# RPi-ShieldBridge_v10.net
KiCad netlist of a schematic drawn in EAGLE
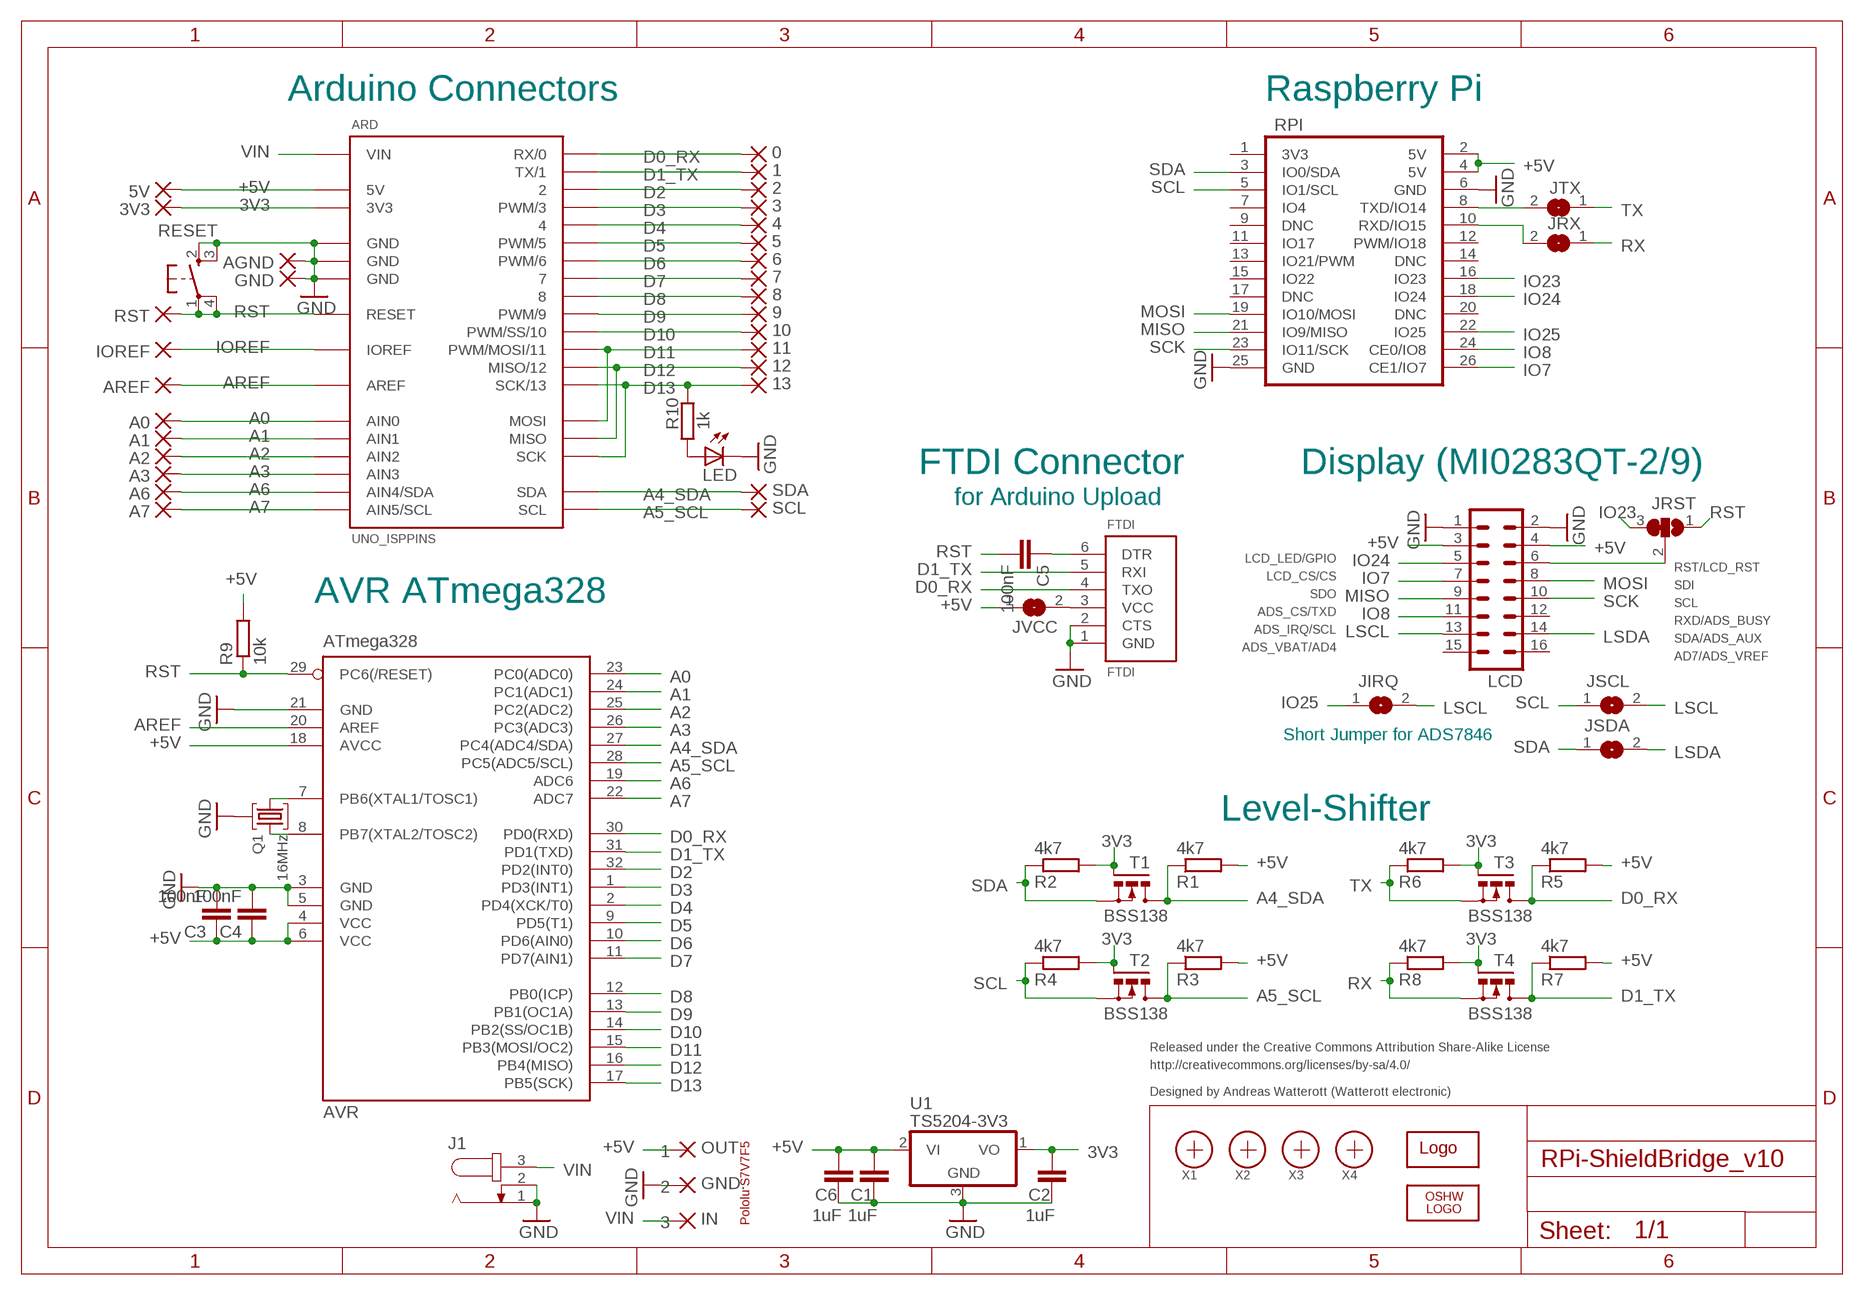
[diagram p0: schematic, sheet 1]

(export (version "E")
  (design (tool "Eeschema 10.0.6"))
  (components
    (comp (ref "0")
      (value "WIREPAD1,6/0,9")
      (footprint "eagle-import:1,6_0,9")
      (libsource (lib "eagle-import") (part "WIREPAD1,6/0,9"))
    )
    (comp (ref "1")
      (value "WIREPAD1,6/0,9")
      (footprint "eagle-import:1,6_0,9")
      (libsource (lib "eagle-import") (part "WIREPAD1,6/0,9"))
    )
    (comp (ref "2")
      (value "WIREPAD1,6/0,9")
      (footprint "eagle-import:1,6_0,9")
      (libsource (lib "eagle-import") (part "WIREPAD1,6/0,9"))
    )
    (comp (ref "3")
      (value "WIREPAD1,6/0,9")
      (footprint "eagle-import:1,6_0,9")
      (libsource (lib "eagle-import") (part "WIREPAD1,6/0,9"))
    )
    (comp (ref "3V3")
      (value "WIREPAD1,6/0,9")
      (footprint "eagle-import:1,6_0,9")
      (libsource (lib "eagle-import") (part "WIREPAD1,6/0,9"))
    )
    (comp (ref "4")
      (value "WIREPAD1,6/0,9")
      (footprint "eagle-import:1,6_0,9")
      (libsource (lib "eagle-import") (part "WIREPAD1,6/0,9"))
    )
    (comp (ref "5")
      (value "WIREPAD1,6/0,9")
      (footprint "eagle-import:1,6_0,9")
      (libsource (lib "eagle-import") (part "WIREPAD1,6/0,9"))
    )
    (comp (ref "5V")
      (value "WIREPAD1,6/0,9")
      (footprint "eagle-import:1,6_0,9")
      (libsource (lib "eagle-import") (part "WIREPAD1,6/0,9"))
    )
    (comp (ref "6")
      (value "WIREPAD1,6/0,9")
      (footprint "eagle-import:1,6_0,9")
      (libsource (lib "eagle-import") (part "WIREPAD1,6/0,9"))
    )
    (comp (ref "7")
      (value "WIREPAD1,6/0,9")
      (footprint "eagle-import:1,6_0,9")
      (libsource (lib "eagle-import") (part "WIREPAD1,6/0,9"))
    )
    (comp (ref "8")
      (value "WIREPAD1,6/0,9")
      (footprint "eagle-import:1,6_0,9")
      (libsource (lib "eagle-import") (part "WIREPAD1,6/0,9"))
    )
    (comp (ref "9")
      (value "WIREPAD1,6/0,9")
      (footprint "eagle-import:1,6_0,9")
      (libsource (lib "eagle-import") (part "WIREPAD1,6/0,9"))
    )
    (comp (ref "10")
      (value "WIREPAD1,6/0,9")
      (footprint "eagle-import:1,6_0,9")
      (libsource (lib "eagle-import") (part "WIREPAD1,6/0,9"))
    )
    (comp (ref "11")
      (value "WIREPAD1,6/0,9")
      (footprint "eagle-import:1,6_0,9")
      (libsource (lib "eagle-import") (part "WIREPAD1,6/0,9"))
    )
    (comp (ref "12")
      (value "WIREPAD1,6/0,9")
      (footprint "eagle-import:1,6_0,9")
      (libsource (lib "eagle-import") (part "WIREPAD1,6/0,9"))
    )
    (comp (ref "13")
      (value "WIREPAD1,6/0,9")
      (footprint "eagle-import:1,6_0,9")
      (libsource (lib "eagle-import") (part "WIREPAD1,6/0,9"))
    )
    (comp (ref "A0")
      (value "WIREPAD1,6/0,9")
      (footprint "eagle-import:1,6_0,9")
      (libsource (lib "eagle-import") (part "WIREPAD1,6/0,9"))
    )
    (comp (ref "A1")
      (value "WIREPAD1,6/0,9")
      (footprint "eagle-import:1,6_0,9")
      (libsource (lib "eagle-import") (part "WIREPAD1,6/0,9"))
    )
    (comp (ref "A2")
      (value "WIREPAD1,6/0,9")
      (footprint "eagle-import:1,6_0,9")
      (libsource (lib "eagle-import") (part "WIREPAD1,6/0,9"))
    )
    (comp (ref "A3")
      (value "WIREPAD1,6/0,9")
      (footprint "eagle-import:1,6_0,9")
      (libsource (lib "eagle-import") (part "WIREPAD1,6/0,9"))
    )
    (comp (ref "A6")
      (value "WIREPAD1,6/0,9")
      (footprint "eagle-import:1,6_0,9")
      (libsource (lib "eagle-import") (part "WIREPAD1,6/0,9"))
    )
    (comp (ref "A7")
      (value "WIREPAD1,6/0,9")
      (footprint "eagle-import:1,6_0,9")
      (libsource (lib "eagle-import") (part "WIREPAD1,6/0,9"))
    )
    (comp (ref "AGND")
      (value "WIREPAD1,6/0,9")
      (footprint "eagle-import:1,6_0,9")
      (libsource (lib "eagle-import") (part "WIREPAD1,6/0,9"))
    )
    (comp (ref "ARD")
      (value "UNO_ISPPINS")
      (footprint "eagle-import:UNO_ISP3")
      (libsource (lib "eagle-import") (part "UNO_ISPPINS"))
    )
    (comp (ref "AREF")
      (value "WIREPAD1,6/0,9")
      (footprint "eagle-import:1,6_0,9")
      (libsource (lib "eagle-import") (part "WIREPAD1,6/0,9"))
    )
    (comp (ref "AVR")
      (value "ATmega328")
      (footprint "eagle-import:TQFP32-08")
      (fields (field (name "MPN") "ATMEGA8-16AU"))
      (libsource (lib "eagle-import") (part "MEGA8-AI"))
    )
    (comp (ref "C1")
      (value "1uF")
      (footprint "eagle-import:C0603")
      (libsource (lib "eagle-import") (part "C-EUC0603"))
    )
    (comp (ref "C2")
      (value "1uF")
      (footprint "eagle-import:C0603")
      (libsource (lib "eagle-import") (part "C-EUC0603"))
    )
    (comp (ref "C3")
      (value "100nF")
      (footprint "eagle-import:C0603")
      (libsource (lib "eagle-import") (part "C-EUC0603"))
    )
    (comp (ref "C4")
      (value "100nF")
      (footprint "eagle-import:C0603")
      (libsource (lib "eagle-import") (part "C-EUC0603"))
    )
    (comp (ref "C5")
      (value "100nF")
      (footprint "eagle-import:C0603")
      (libsource (lib "eagle-import") (part "C-EUC0603"))
    )
    (comp (ref "C6")
      (value "1uF")
      (footprint "eagle-import:C0603")
      (libsource (lib "eagle-import") (part "C-EUC0603"))
    )
    (comp (ref "FTDI")
      (value "FTDI")
      (footprint "eagle-import:FTDI")
      (libsource (lib "eagle-import") (part "FTDI"))
    )
    (comp (ref "GND")
      (value "WIREPAD1,6/0,9")
      (footprint "eagle-import:1,6_0,9")
      (libsource (lib "eagle-import") (part "WIREPAD1,6/0,9"))
    )
    (comp (ref "GND.")
      (value "2")
      (footprint "eagle-import:1,6_0,9")
      (libsource (lib "eagle-import") (part "WIREPAD1,6/0,9"))
    )
    (comp (ref "IN")
      (value "3")
      (footprint "eagle-import:1,6_0,9")
      (libsource (lib "eagle-import") (part "WIREPAD1,6/0,9"))
    )
    (comp (ref "IOREF")
      (value "WIREPAD1,6/0,9")
      (footprint "eagle-import:1,6_0,9")
      (libsource (lib "eagle-import") (part "WIREPAD1,6/0,9"))
    )
    (comp (ref "J1")
      (value "DC-JACK\"\"")
      (footprint "eagle-import:DC-JACK")
      (libsource (lib "eagle-import") (part "DC-JACK{dblquote}{dblquote}"))
    )
    (comp (ref "JIRQ")
      (value "SJ")
      (footprint "eagle-import:SJ")
      (libsource (lib "eagle-import") (part "SJ"))
    )
    (comp (ref "JRST")
      (value "SJ2W")
      (footprint "eagle-import:SJ_2")
      (libsource (lib "eagle-import") (part "SJ2W"))
    )
    (comp (ref "JRX") (value "SJ") (footprint "eagle-import:SJ") (libsource (lib "eagle-import") (part "SJ")))
    (comp (ref "JSCL")
      (value "SJ")
      (footprint "eagle-import:SJ")
      (libsource (lib "eagle-import") (part "SJ"))
    )
    (comp (ref "JSDA")
      (value "SJ")
      (footprint "eagle-import:SJ")
      (libsource (lib "eagle-import") (part "SJ"))
    )
    (comp (ref "JTX") (value "SJ") (footprint "eagle-import:SJ") (libsource (lib "eagle-import") (part "SJ")))
    (comp (ref "JVCC")
      (value "SJ")
      (footprint "eagle-import:SJ")
      (libsource (lib "eagle-import") (part "SJ"))
    )
    (comp (ref "LCD")
      (value "MA08-2")
      (footprint "eagle-import:MA08-2")
      (libsource (lib "eagle-import") (part "MA08-2"))
    )
    (comp (ref "LED")
      (value "LEDCHIPLED_0603")
      (footprint "eagle-import:CHIPLED_0603")
      (libsource (lib "eagle-import") (part "LEDCHIPLED_0603"))
    )
    (comp (ref "LOGO1")
      (value "OSHW_LOGO_6MILX0150-NT")
      (footprint "eagle-import:OSHW_6X150_NOTEXT")
      (libsource (lib "eagle-import") (part "OSHW_LOGO_6MILX0150-NT"))
    )
    (comp (ref "OUT")
      (value "1")
      (footprint "eagle-import:1,6_0,9")
      (libsource (lib "eagle-import") (part "WIREPAD1,6/0,9"))
    )
    (comp (ref "Q1")
      (value "16MHz")
      (footprint "eagle-import:SMD_OSC_35X15")
      (libsource (lib "eagle-import") (part "SMD_OSC2"))
    )
    (comp (ref "R1")
      (value "4k7")
      (footprint "eagle-import:R0603")
      (libsource (lib "eagle-import") (part "R-EU_R0603"))
    )
    (comp (ref "R2")
      (value "4k7")
      (footprint "eagle-import:R0603")
      (libsource (lib "eagle-import") (part "R-EU_R0603"))
    )
    (comp (ref "R3")
      (value "4k7")
      (footprint "eagle-import:R0603")
      (libsource (lib "eagle-import") (part "R-EU_R0603"))
    )
    (comp (ref "R4")
      (value "4k7")
      (footprint "eagle-import:R0603")
      (libsource (lib "eagle-import") (part "R-EU_R0603"))
    )
    (comp (ref "R5")
      (value "4k7")
      (footprint "eagle-import:R0603")
      (libsource (lib "eagle-import") (part "R-EU_R0603"))
    )
    (comp (ref "R6")
      (value "4k7")
      (footprint "eagle-import:R0603")
      (libsource (lib "eagle-import") (part "R-EU_R0603"))
    )
    (comp (ref "R7")
      (value "4k7")
      (footprint "eagle-import:R0603")
      (libsource (lib "eagle-import") (part "R-EU_R0603"))
    )
    (comp (ref "R8")
      (value "4k7")
      (footprint "eagle-import:R0603")
      (libsource (lib "eagle-import") (part "R-EU_R0603"))
    )
    (comp (ref "R9")
      (value "10k")
      (footprint "eagle-import:R0603")
      (libsource (lib "eagle-import") (part "R-EU_R0603"))
    )
    (comp (ref "R10")
      (value "1k")
      (footprint "eagle-import:R0603")
      (libsource (lib "eagle-import") (part "R-EU_R0603"))
    )
    (comp (ref "RESET")
      (value "SW_SMDS")
      (footprint "eagle-import:SW_SMD4@1")
      (libsource (lib "eagle-import") (part "SW_SMDS"))
    )
    (comp (ref "RPI")
      (value "RPI")
      (footprint "eagle-import:RPI")
      (libsource (lib "eagle-import") (part "RPI"))
    )
    (comp (ref "RST")
      (value "WIREPAD1,6/0,9")
      (footprint "eagle-import:1,6_0,9")
      (libsource (lib "eagle-import") (part "WIREPAD1,6/0,9"))
    )
    (comp (ref "SCL")
      (value "WIREPAD1,6/0,9")
      (footprint "eagle-import:1,6_0,9")
      (libsource (lib "eagle-import") (part "WIREPAD1,6/0,9"))
    )
    (comp (ref "SDA")
      (value "WIREPAD1,6/0,9")
      (footprint "eagle-import:1,6_0,9")
      (libsource (lib "eagle-import") (part "WIREPAD1,6/0,9"))
    )
    (comp (ref "T1")
      (value "BSS138")
      (footprint "eagle-import:MICRO3")
      (libsource (lib "eagle-import") (part "IRLML2502"))
    )
    (comp (ref "T2")
      (value "BSS138")
      (footprint "eagle-import:MICRO3")
      (libsource (lib "eagle-import") (part "IRLML2502"))
    )
    (comp (ref "T3")
      (value "BSS138")
      (footprint "eagle-import:MICRO3")
      (libsource (lib "eagle-import") (part "IRLML2502"))
    )
    (comp (ref "T4")
      (value "BSS138")
      (footprint "eagle-import:MICRO3")
      (libsource (lib "eagle-import") (part "IRLML2502"))
    )
    (comp (ref "U$1")
      (value "WE-LOGO")
      (footprint "eagle-import:WE-LOGO")
      (libsource (lib "eagle-import") (part "WE-LOGOPLACE"))
    )
    (comp (ref "U1")
      (value "TS5204-3V3")
      (footprint "eagle-import:SOT23")
      (libsource (lib "eagle-import") (part "TS5204"))
    )
    (comp (ref "X1")
      (value "PASSER")
      (footprint "eagle-import:PASSER")
      (libsource (lib "eagle-import") (part "PASSER"))
    )
    (comp (ref "X2")
      (value "PASSER")
      (footprint "eagle-import:PASSER")
      (libsource (lib "eagle-import") (part "PASSER"))
    )
    (comp (ref "X3")
      (value "PASSER")
      (footprint "eagle-import:PASSER")
      (libsource (lib "eagle-import") (part "PASSER"))
    )
    (comp (ref "X4")
      (value "PASSER")
      (footprint "eagle-import:PASSER")
      (libsource (lib "eagle-import") (part "PASSER"))
    )
  )
  (nets
    (net (code "1") (name "/+5V") (class "Default")
      (node (ref "5V") (pin "1") (pinfunction "P_1") (pintype "passive"))
      (node (ref "ARD") (pin "5V") (pinfunction "5V_5V") (pintype "power_in"))
      (node (ref "AVR") (pin "18") (pinfunction "AVCC_18") (pintype "power_in"))
      (node (ref "AVR") (pin "4") (pinfunction "VCC_4") (pintype "power_in"))
      (node (ref "AVR") (pin "6") (pinfunction "VCC_6") (pintype "power_in"))
      (node (ref "C1") (pin "1") (pinfunction "1_1") (pintype "passive"))
      (node (ref "C3") (pin "1") (pinfunction "1_1") (pintype "passive"))
      (node (ref "C4") (pin "1") (pinfunction "1_1") (pintype "passive"))
      (node (ref "C6") (pin "1") (pinfunction "1_1") (pintype "passive"))
      (node (ref "JVCC") (pin "1") (pinfunction "1_1") (pintype "passive"))
      (node (ref "LCD") (pin "3") (pinfunction "3_3") (pintype "passive"))
      (node (ref "LCD") (pin "4") (pinfunction "4_4") (pintype "passive"))
      (node (ref "OUT") (pin "1") (pinfunction "P_1") (pintype "passive"))
      (node (ref "R1") (pin "2") (pinfunction "2_2") (pintype "passive"))
      (node (ref "R3") (pin "2") (pinfunction "2_2") (pintype "passive"))
      (node (ref "R5") (pin "2") (pinfunction "2_2") (pintype "passive"))
      (node (ref "R7") (pin "2") (pinfunction "2_2") (pintype "passive"))
      (node (ref "R9") (pin "2") (pinfunction "2_2") (pintype "passive"))
      (node (ref "RPI") (pin "2") (pinfunction "5V_2") (pintype "passive"))
      (node (ref "RPI") (pin "4") (pinfunction "5V_4") (pintype "passive"))
      (node (ref "U1") (pin "2") (pinfunction "VI_2") (pintype "input"))
    )
    (net (code "2") (name "/3V3") (class "Default")
      (node (ref "3V3") (pin "1") (pinfunction "P_1") (pintype "passive"))
      (node (ref "ARD") (pin "3V3") (pinfunction "3V3_3V3") (pintype "power_in"))
      (node (ref "C2") (pin "1") (pinfunction "1_1") (pintype "passive"))
      (node (ref "R2") (pin "2") (pinfunction "2_2") (pintype "passive"))
      (node (ref "R4") (pin "2") (pinfunction "2_2") (pintype "passive"))
      (node (ref "R6") (pin "2") (pinfunction "2_2") (pintype "passive"))
      (node (ref "R8") (pin "2") (pinfunction "2_2") (pintype "passive"))
      (node (ref "T1") (pin "1") (pinfunction "G_1") (pintype "passive"))
      (node (ref "T2") (pin "1") (pinfunction "G_1") (pintype "passive"))
      (node (ref "T3") (pin "1") (pinfunction "G_1") (pintype "passive"))
      (node (ref "T4") (pin "1") (pinfunction "G_1") (pintype "passive"))
      (node (ref "U1") (pin "1") (pinfunction "VO_1") (pintype "passive"))
    )
    (net (code "3") (name "/A0") (class "Default")
      (node (ref "A0") (pin "1") (pinfunction "P_1") (pintype "passive"))
      (node (ref "ARD") (pin "AIN0") (pinfunction "AIN0_AIN0") (pintype "bidirectional"))
      (node (ref "AVR") (pin "23") (pinfunction "PC0(ADC0)_23") (pintype "bidirectional"))
    )
    (net (code "4") (name "/A1") (class "Default")
      (node (ref "A1") (pin "1") (pinfunction "P_1") (pintype "passive"))
      (node (ref "ARD") (pin "AIN1") (pinfunction "AIN1_AIN1") (pintype "bidirectional"))
      (node (ref "AVR") (pin "24") (pinfunction "PC1(ADC1)_24") (pintype "bidirectional"))
    )
    (net (code "5") (name "/A2") (class "Default")
      (node (ref "A2") (pin "1") (pinfunction "P_1") (pintype "passive"))
      (node (ref "ARD") (pin "AIN2") (pinfunction "AIN2_AIN2") (pintype "bidirectional"))
      (node (ref "AVR") (pin "25") (pinfunction "PC2(ADC2)_25") (pintype "bidirectional"))
    )
    (net (code "6") (name "/A3") (class "Default")
      (node (ref "A3") (pin "1") (pinfunction "P_1") (pintype "passive"))
      (node (ref "ARD") (pin "AIN3") (pinfunction "AIN3_AIN3") (pintype "bidirectional"))
      (node (ref "AVR") (pin "26") (pinfunction "PC3(ADC3)_26") (pintype "bidirectional"))
    )
    (net (code "7") (name "/A4_SDA") (class "Default")
      (node (ref "ARD") (pin "SDA") (pinfunction "SDA_SDA") (pintype "bidirectional"))
      (node (ref "AVR") (pin "27") (pinfunction "PC4(ADC4/SDA)_27") (pintype "bidirectional"))
      (node (ref "R1") (pin "1") (pinfunction "1_1") (pintype "passive"))
      (node (ref "SDA") (pin "1") (pinfunction "P_1") (pintype "passive"))
      (node (ref "T1") (pin "3") (pinfunction "D_3") (pintype "passive"))
    )
    (net (code "8") (name "/A5_SCL") (class "Default")
      (node (ref "ARD") (pin "SCL") (pinfunction "SCL_SCL") (pintype "bidirectional"))
      (node (ref "AVR") (pin "28") (pinfunction "PC5(ADC5/SCL)_28") (pintype "bidirectional"))
      (node (ref "R3") (pin "1") (pinfunction "1_1") (pintype "passive"))
      (node (ref "SCL") (pin "1") (pinfunction "P_1") (pintype "passive"))
      (node (ref "T2") (pin "3") (pinfunction "D_3") (pintype "passive"))
    )
    (net (code "9") (name "/A6") (class "Default")
      (node (ref "A6") (pin "1") (pinfunction "P_1") (pintype "passive"))
      (node (ref "ARD") (pin "AIN4") (pinfunction "AIN4/SDA_AIN4") (pintype "bidirectional"))
      (node (ref "AVR") (pin "19") (pinfunction "ADC6_19") (pintype "bidirectional"))
    )
    (net (code "10") (name "/A7") (class "Default")
      (node (ref "A7") (pin "1") (pinfunction "P_1") (pintype "passive"))
      (node (ref "ARD") (pin "AIN5") (pinfunction "AIN5/SCL_AIN5") (pintype "bidirectional"))
      (node (ref "AVR") (pin "22") (pinfunction "ADC7_22") (pintype "bidirectional"))
    )
    (net (code "11") (name "/AREF") (class "Default")
      (node (ref "ARD") (pin "AREF") (pinfunction "AREF_AREF") (pintype "power_in"))
      (node (ref "AREF") (pin "1") (pinfunction "P_1") (pintype "passive"))
      (node (ref "AVR") (pin "20") (pinfunction "AREF_20") (pintype "passive"))
    )
    (net (code "12") (name "/D0_RX") (class "Default")
      (node (ref "0") (pin "1") (pinfunction "P_1") (pintype "passive"))
      (node (ref "ARD") (pin "0") (pinfunction "RX/0_0") (pintype "bidirectional"))
      (node (ref "AVR") (pin "30") (pinfunction "PD0(RXD)_30") (pintype "bidirectional"))
      (node (ref "FTDI") (pin "4") (pinfunction "TXO_4") (pintype "bidirectional"))
      (node (ref "R5") (pin "1") (pinfunction "1_1") (pintype "passive"))
      (node (ref "T3") (pin "3") (pinfunction "D_3") (pintype "passive"))
    )
    (net (code "13") (name "/D1_TX") (class "Default")
      (node (ref "1") (pin "1") (pinfunction "P_1") (pintype "passive"))
      (node (ref "ARD") (pin "1") (pinfunction "TX/1_1") (pintype "bidirectional"))
      (node (ref "AVR") (pin "31") (pinfunction "PD1(TXD)_31") (pintype "bidirectional"))
      (node (ref "FTDI") (pin "5") (pinfunction "RXI_5") (pintype "bidirectional"))
      (node (ref "R7") (pin "1") (pinfunction "1_1") (pintype "passive"))
      (node (ref "T4") (pin "3") (pinfunction "D_3") (pintype "passive"))
    )
    (net (code "14") (name "/D2") (class "Default")
      (node (ref "2") (pin "1") (pinfunction "P_1") (pintype "passive"))
      (node (ref "ARD") (pin "2") (pinfunction "2_2") (pintype "bidirectional"))
      (node (ref "AVR") (pin "32") (pinfunction "PD2(INT0)_32") (pintype "bidirectional"))
    )
    (net (code "15") (name "/D3") (class "Default")
      (node (ref "3") (pin "1") (pinfunction "P_1") (pintype "passive"))
      (node (ref "ARD") (pin "3") (pinfunction "PWM/3_3") (pintype "bidirectional"))
      (node (ref "AVR") (pin "1") (pinfunction "PD3(INT1)_1") (pintype "bidirectional"))
    )
    (net (code "16") (name "/D4") (class "Default")
      (node (ref "4") (pin "1") (pinfunction "P_1") (pintype "passive"))
      (node (ref "ARD") (pin "4") (pinfunction "4_4") (pintype "bidirectional"))
      (node (ref "AVR") (pin "2") (pinfunction "PD4(XCK/T0)_2") (pintype "bidirectional"))
    )
    (net (code "17") (name "/D5") (class "Default")
      (node (ref "5") (pin "1") (pinfunction "P_1") (pintype "passive"))
      (node (ref "ARD") (pin "5") (pinfunction "PWM/5_5") (pintype "bidirectional"))
      (node (ref "AVR") (pin "9") (pinfunction "PD5(T1)_9") (pintype "bidirectional"))
    )
    (net (code "18") (name "/D6") (class "Default")
      (node (ref "6") (pin "1") (pinfunction "P_1") (pintype "passive"))
      (node (ref "ARD") (pin "6") (pinfunction "PWM/6_6") (pintype "bidirectional"))
      (node (ref "AVR") (pin "10") (pinfunction "PD6(AIN0)_10") (pintype "bidirectional"))
    )
    (net (code "19") (name "/D7") (class "Default")
      (node (ref "7") (pin "1") (pinfunction "P_1") (pintype "passive"))
      (node (ref "ARD") (pin "7") (pinfunction "7_7") (pintype "bidirectional"))
      (node (ref "AVR") (pin "11") (pinfunction "PD7(AIN1)_11") (pintype "bidirectional"))
    )
    (net (code "20") (name "/D8") (class "Default")
      (node (ref "8") (pin "1") (pinfunction "P_1") (pintype "passive"))
      (node (ref "ARD") (pin "8") (pinfunction "8_8") (pintype "bidirectional"))
      (node (ref "AVR") (pin "12") (pinfunction "PB0(ICP)_12") (pintype "bidirectional"))
    )
    (net (code "21") (name "/D9") (class "Default")
      (node (ref "9") (pin "1") (pinfunction "P_1") (pintype "passive"))
      (node (ref "ARD") (pin "9") (pinfunction "PWM/9_9") (pintype "bidirectional"))
      (node (ref "AVR") (pin "13") (pinfunction "PB1(OC1A)_13") (pintype "bidirectional"))
    )
    (net (code "22") (name "/D10") (class "Default")
      (node (ref "10") (pin "1") (pinfunction "P_1") (pintype "passive"))
      (node (ref "ARD") (pin "10") (pinfunction "PWM/SS/10_10") (pintype "bidirectional"))
      (node (ref "AVR") (pin "14") (pinfunction "PB2(SS/OC1B)_14") (pintype "bidirectional"))
    )
    (net (code "23") (name "/D11") (class "Default")
      (node (ref "11") (pin "1") (pinfunction "P_1") (pintype "passive"))
      (node (ref "ARD") (pin "11") (pinfunction "PWM/MOSI/11_11") (pintype "bidirectional"))
      (node (ref "ARD") (pin "MOSI") (pinfunction "MOSI_MOSI") (pintype "bidirectional"))
      (node (ref "AVR") (pin "15") (pinfunction "PB3(MOSI/OC2)_15") (pintype "bidirectional"))
    )
    (net (code "24") (name "/D12") (class "Default")
      (node (ref "12") (pin "1") (pinfunction "P_1") (pintype "passive"))
      (node (ref "ARD") (pin "12") (pinfunction "MISO/12_12") (pintype "bidirectional"))
      (node (ref "ARD") (pin "MISO") (pinfunction "MISO_MISO") (pintype "bidirectional"))
      (node (ref "AVR") (pin "16") (pinfunction "PB4(MISO)_16") (pintype "bidirectional"))
    )
    (net (code "25") (name "/D13") (class "Default")
      (node (ref "13") (pin "1") (pinfunction "P_1") (pintype "passive"))
      (node (ref "ARD") (pin "13") (pinfunction "SCK/13_13") (pintype "bidirectional"))
      (node (ref "ARD") (pin "SCK") (pinfunction "SCK_SCK") (pintype "bidirectional"))
      (node (ref "AVR") (pin "17") (pinfunction "PB5(SCK)_17") (pintype "bidirectional"))
      (node (ref "R10") (pin "1") (pinfunction "1_1") (pintype "passive"))
    )
    (net (code "26") (name "/IO7") (class "Default")
      (node (ref "LCD") (pin "7") (pinfunction "7_7") (pintype "passive"))
      (node (ref "RPI") (pin "26") (pinfunction "CE1/IO7_26") (pintype "passive"))
    )
    (net (code "27") (name "/IO8") (class "Default")
      (node (ref "LCD") (pin "11") (pinfunction "11_11") (pintype "passive"))
      (node (ref "RPI") (pin "24") (pinfunction "CE0/IO8_24") (pintype "passive"))
    )
    (net (code "28") (name "/IO23") (class "Default")
      (node (ref "JRST") (pin "3") (pinfunction "3_3") (pintype "passive"))
      (node (ref "RPI") (pin "16") (pinfunction "IO23_16") (pintype "passive"))
    )
    (net (code "29") (name "/IO24") (class "Default")
      (node (ref "LCD") (pin "5") (pinfunction "5_5") (pintype "passive"))
      (node (ref "RPI") (pin "18") (pinfunction "IO24_18") (pintype "passive"))
    )
    (net (code "30") (name "/IO25") (class "Default")
      (node (ref "JIRQ") (pin "1") (pinfunction "1_1") (pintype "passive"))
      (node (ref "RPI") (pin "22") (pinfunction "IO25_22") (pintype "passive"))
    )
    (net (code "31") (name "/IOREF") (class "Default")
      (node (ref "ARD") (pin "IOREF") (pinfunction "IOREF_IOREF") (pintype "power_in"))
      (node (ref "IOREF") (pin "1") (pinfunction "P_1") (pintype "passive"))
    )
    (net (code "32") (name "/LSCL") (class "Default")
      (node (ref "JIRQ") (pin "2") (pinfunction "2_2") (pintype "passive"))
      (node (ref "JSCL") (pin "2") (pinfunction "2_2") (pintype "passive"))
      (node (ref "LCD") (pin "13") (pinfunction "13_13") (pintype "passive"))
    )
    (net (code "33") (name "/LSDA") (class "Default")
      (node (ref "JSDA") (pin "2") (pinfunction "2_2") (pintype "passive"))
      (node (ref "LCD") (pin "14") (pinfunction "14_14") (pintype "passive"))
    )
    (net (code "34") (name "/MISO") (class "Default")
      (node (ref "LCD") (pin "9") (pinfunction "9_9") (pintype "passive"))
      (node (ref "RPI") (pin "21") (pinfunction "IO9/MISO_21") (pintype "passive"))
    )
    (net (code "35") (name "/MOSI") (class "Default")
      (node (ref "LCD") (pin "8") (pinfunction "8_8") (pintype "passive"))
      (node (ref "RPI") (pin "19") (pinfunction "IO10/MOSI_19") (pintype "passive"))
    )
    (net (code "36") (name "/RST") (class "Default")
      (node (ref "ARD") (pin "RST") (pinfunction "RESET_RST") (pintype "bidirectional"))
      (node (ref "AVR") (pin "29") (pinfunction "PC6(/RESET)_29") (pintype "bidirectional"))
      (node (ref "C5") (pin "2") (pinfunction "2_2") (pintype "passive"))
      (node (ref "JRST") (pin "1") (pinfunction "1_1") (pintype "passive"))
      (node (ref "R9") (pin "1") (pinfunction "1_1") (pintype "passive"))
      (node (ref "RESET") (pin "1") (pinfunction "P_1") (pintype "passive"))
      (node (ref "RESET") (pin "4") (pinfunction "P1_4") (pintype "passive"))
      (node (ref "RST") (pin "1") (pinfunction "P_1") (pintype "passive"))
    )
    (net (code "37") (name "/RX") (class "Default")
      (node (ref "JRX") (pin "1") (pinfunction "1_1") (pintype "passive"))
      (node (ref "R8") (pin "1") (pinfunction "1_1") (pintype "passive"))
      (node (ref "T4") (pin "2") (pinfunction "S_2") (pintype "passive"))
    )
    (net (code "38") (name "/SCK") (class "Default")
      (node (ref "LCD") (pin "10") (pinfunction "10_10") (pintype "passive"))
      (node (ref "RPI") (pin "23") (pinfunction "IO11/SCK_23") (pintype "passive"))
    )
    (net (code "39") (name "/SCL") (class "Default")
      (node (ref "JSCL") (pin "1") (pinfunction "1_1") (pintype "passive"))
      (node (ref "R4") (pin "1") (pinfunction "1_1") (pintype "passive"))
      (node (ref "RPI") (pin "5") (pinfunction "IO1/SCL_5") (pintype "passive"))
      (node (ref "T2") (pin "2") (pinfunction "S_2") (pintype "passive"))
    )
    (net (code "40") (name "/SDA") (class "Default")
      (node (ref "JSDA") (pin "1") (pinfunction "1_1") (pintype "passive"))
      (node (ref "R2") (pin "1") (pinfunction "1_1") (pintype "passive"))
      (node (ref "RPI") (pin "3") (pinfunction "IO0/SDA_3") (pintype "passive"))
      (node (ref "T1") (pin "2") (pinfunction "S_2") (pintype "passive"))
    )
    (net (code "41") (name "/TX") (class "Default")
      (node (ref "JTX") (pin "1") (pinfunction "1_1") (pintype "passive"))
      (node (ref "R6") (pin "1") (pinfunction "1_1") (pintype "passive"))
      (node (ref "T3") (pin "2") (pinfunction "S_2") (pintype "passive"))
    )
    (net (code "42") (name "/VIN") (class "Default")
      (node (ref "ARD") (pin "VIN") (pinfunction "VIN_VIN") (pintype "power_in"))
      (node (ref "IN") (pin "1") (pinfunction "P_1") (pintype "passive"))
      (node (ref "J1") (pin "3") (pinfunction "3_3") (pintype "passive"))
    )
    (net (code "43") (name "GND") (class "Default")
      (node (ref "AGND") (pin "1") (pinfunction "P_1") (pintype "passive"))
      (node (ref "ARD") (pin "GND@1") (pinfunction "GND_GND@1") (pintype "power_in"))
      (node (ref "ARD") (pin "GND@2") (pinfunction "GND_GND@2") (pintype "power_in"))
      (node (ref "ARD") (pin "GND@3") (pinfunction "GND_GND@3") (pintype "power_in"))
      (node (ref "AVR") (pin "21") (pinfunction "GND_21") (pintype "power_in"))
      (node (ref "AVR") (pin "3") (pinfunction "GND_3") (pintype "power_in"))
      (node (ref "AVR") (pin "5") (pinfunction "GND_5") (pintype "power_in"))
      (node (ref "C1") (pin "2") (pinfunction "2_2") (pintype "passive"))
      (node (ref "C2") (pin "2") (pinfunction "2_2") (pintype "passive"))
      (node (ref "C3") (pin "2") (pinfunction "2_2") (pintype "passive"))
      (node (ref "C4") (pin "2") (pinfunction "2_2") (pintype "passive"))
      (node (ref "C6") (pin "2") (pinfunction "2_2") (pintype "passive"))
      (node (ref "FTDI") (pin "1") (pinfunction "GND_1") (pintype "bidirectional"))
      (node (ref "FTDI") (pin "2") (pinfunction "CTS_2") (pintype "bidirectional"))
      (node (ref "GND") (pin "1") (pinfunction "P_1") (pintype "passive"))
      (node (ref "GND.") (pin "1") (pinfunction "P_1") (pintype "passive"))
      (node (ref "J1") (pin "1") (pinfunction "1_1") (pintype "passive"))
      (node (ref "J1") (pin "2") (pinfunction "2_2") (pintype "passive"))
      (node (ref "LCD") (pin "1") (pinfunction "1_1") (pintype "passive"))
      (node (ref "LCD") (pin "2") (pinfunction "2_2") (pintype "passive"))
      (node (ref "LED") (pin "C") (pinfunction "C_C") (pintype "passive"))
      (node (ref "Q1") (pin "GND") (pinfunction "GND_GND") (pintype "passive"))
      (node (ref "RESET") (pin "2") (pinfunction "S_2") (pintype "passive"))
      (node (ref "RESET") (pin "3") (pinfunction "S1_3") (pintype "passive"))
      (node (ref "RPI") (pin "25") (pinfunction "GND_25") (pintype "passive"))
      (node (ref "RPI") (pin "6") (pinfunction "GND_6") (pintype "passive"))
      (node (ref "U1") (pin "3") (pinfunction "GND_3") (pintype "passive"))
    )
    (net (code "44") (name "Net-(AVR-PB6(XTAL1{slash}TOSC1))") (class "Default")
      (node (ref "AVR") (pin "7") (pinfunction "PB6(XTAL1/TOSC1)_7") (pintype "bidirectional"))
      (node (ref "Q1") (pin "1") (pinfunction "1_1") (pintype "passive"))
    )
    (net (code "45") (name "Net-(AVR-PB7(XTAL2{slash}TOSC2))") (class "Default")
      (node (ref "AVR") (pin "8") (pinfunction "PB7(XTAL2/TOSC2)_8") (pintype "bidirectional"))
      (node (ref "Q1") (pin "2") (pinfunction "2_2") (pintype "passive"))
    )
    (net (code "46") (name "Net-(FTDI-DTR)") (class "Default")
      (node (ref "C5") (pin "1") (pinfunction "1_1") (pintype "passive"))
      (node (ref "FTDI") (pin "6") (pinfunction "DTR_6") (pintype "bidirectional"))
    )
    (net (code "47") (name "Net-(FTDI-VCC)") (class "Default")
      (node (ref "FTDI") (pin "3") (pinfunction "VCC_3") (pintype "bidirectional"))
      (node (ref "JVCC") (pin "2") (pinfunction "2_2") (pintype "passive"))
    )
    (net (code "48") (name "Net-(JRST-Pad2)") (class "Default")
      (node (ref "JRST") (pin "2") (pinfunction "2_2") (pintype "passive"))
      (node (ref "LCD") (pin "6") (pinfunction "6_6") (pintype "passive"))
    )
    (net (code "49") (name "Net-(LED-PadA)") (class "Default")
      (node (ref "LED") (pin "A") (pinfunction "A_A") (pintype "passive"))
      (node (ref "R10") (pin "2") (pinfunction "2_2") (pintype "passive"))
    )
    (net (code "50") (name "Net-(RPI-RXD{slash}IO15)") (class "Default")
      (node (ref "JRX") (pin "2") (pinfunction "2_2") (pintype "passive"))
      (node (ref "RPI") (pin "10") (pinfunction "RXD/IO15_10") (pintype "passive"))
    )
    (net (code "51") (name "Net-(RPI-TXD{slash}IO14)") (class "Default")
      (node (ref "JTX") (pin "2") (pinfunction "2_2") (pintype "passive"))
      (node (ref "RPI") (pin "8") (pinfunction "TXD/IO14_8") (pintype "passive"))
    )
    (net (code "52") (name "unconnected-(LCD-Pad12)") (class "Default")
      (node (ref "LCD") (pin "12") (pinfunction "12_12") (pintype "passive"))
    )
    (net (code "53") (name "unconnected-(LCD-Pad15)") (class "Default")
      (node (ref "LCD") (pin "15") (pinfunction "15_15") (pintype "passive"))
    )
    (net (code "54") (name "unconnected-(LCD-Pad16)") (class "Default")
      (node (ref "LCD") (pin "16") (pinfunction "16_16") (pintype "passive"))
    )
    (net (code "55") (name "unconnected-(RPI-3V3-Pad1)") (class "Default")
      (node (ref "RPI") (pin "1") (pinfunction "3V3_1") (pintype "passive"))
    )
    (net (code "56") (name "unconnected-(RPI-DNC-Pad9)") (class "Default")
      (node (ref "RPI") (pin "9") (pinfunction "DNC_9") (pintype "passive"))
    )
    (net (code "57") (name "unconnected-(RPI-DNC-Pad14)") (class "Default")
      (node (ref "RPI") (pin "14") (pinfunction "DNC_14") (pintype "passive"))
    )
    (net (code "58") (name "unconnected-(RPI-DNC-Pad17)") (class "Default")
      (node (ref "RPI") (pin "17") (pinfunction "DNC_17") (pintype "passive"))
    )
    (net (code "59") (name "unconnected-(RPI-DNC-Pad20)") (class "Default")
      (node (ref "RPI") (pin "20") (pinfunction "DNC_20") (pintype "passive"))
    )
    (net (code "60") (name "unconnected-(RPI-IO4-Pad7)") (class "Default")
      (node (ref "RPI") (pin "7") (pinfunction "IO4_7") (pintype "passive"))
    )
    (net (code "61") (name "unconnected-(RPI-IO17-Pad11)") (class "Default")
      (node (ref "RPI") (pin "11") (pinfunction "IO17_11") (pintype "passive"))
    )
    (net (code "62") (name "unconnected-(RPI-IO21{slash}PWM-Pad13)") (class "Default")
      (node (ref "RPI") (pin "13") (pinfunction "IO21/PWM_13") (pintype "passive"))
    )
    (net (code "63") (name "unconnected-(RPI-IO22-Pad15)") (class "Default")
      (node (ref "RPI") (pin "15") (pinfunction "IO22_15") (pintype "passive"))
    )
    (net (code "64") (name "unconnected-(RPI-PWM{slash}IO18-Pad12)") (class "Default")
      (node (ref "RPI") (pin "12") (pinfunction "PWM/IO18_12") (pintype "passive"))
    )
  )
)
